# DBSchematics.net
KiCad netlist of a schematic drawn in EAGLE
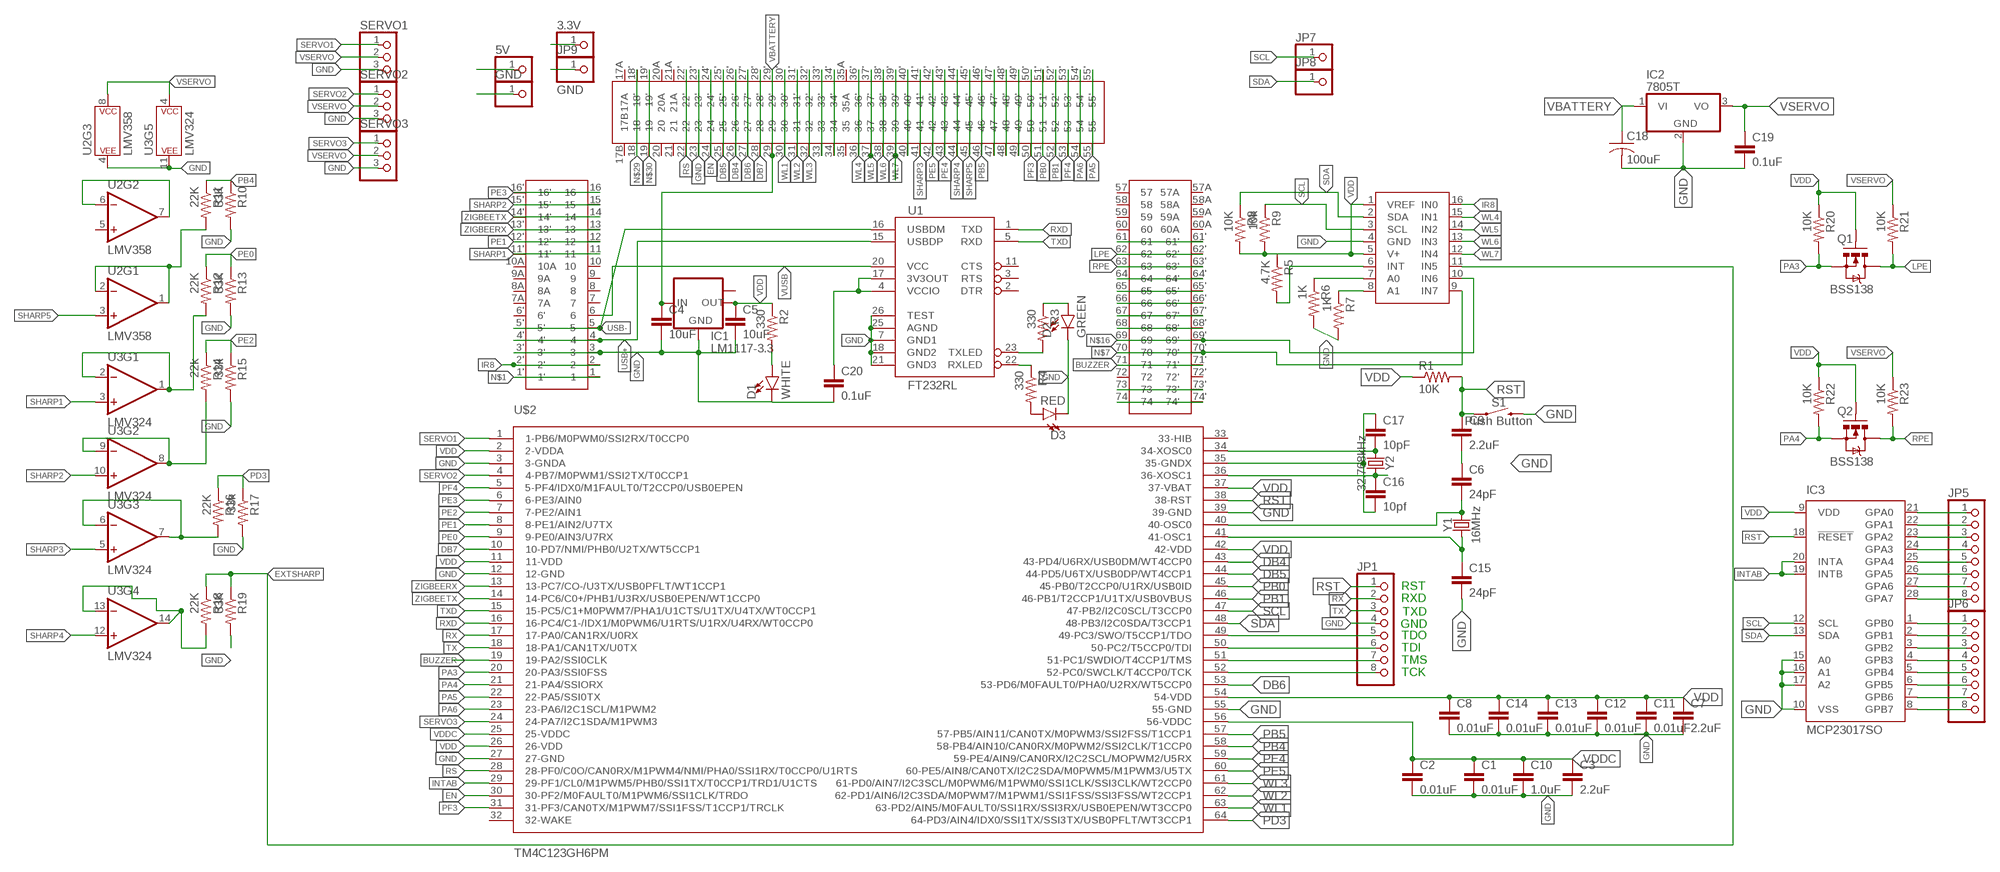
[diagram p0: schematic, sheet 1]

(export (version "E")
  (design (tool "Eeschema 10.0.6"))
  (components
    (comp (ref "3.3V")
      (value "PINHD-1X1")
      (footprint "eagle-import:1X01")
      (libsource (lib "eagle-import") (part "PINHD-1X1"))
    )
    (comp (ref "5V")
      (value "PINHD-1X1")
      (footprint "eagle-import:1X01")
      (libsource (lib "eagle-import") (part "PINHD-1X1"))
    )
    (comp (ref "C1")
      (value "0.01uF")
      (footprint "eagle-import:1206")
      (libsource (lib "eagle-import") (part "2.2UF-CERCAP-10009"))
    )
    (comp (ref "C2")
      (value "0.01uF")
      (footprint "eagle-import:1206")
      (libsource (lib "eagle-import") (part "2.2UF-CERCAP-10009"))
    )
    (comp (ref "C3")
      (value "2.2uF")
      (footprint "eagle-import:1206")
      (libsource (lib "eagle-import") (part "2.2UF-1206-50V-10%"))
    )
    (comp (ref "C4")
      (value "10uF")
      (footprint "eagle-import:1206")
      (libsource (lib "eagle-import") (part "10UF-1206-6.3V-20%"))
    )
    (comp (ref "C5")
      (value "10uF")
      (footprint "eagle-import:1206")
      (libsource (lib "eagle-import") (part "10UF-1206-6.3V-20%"))
    )
    (comp (ref "C6")
      (value "24pF")
      (footprint "eagle-import:1206")
      (libsource (lib "eagle-import") (part "2.2UF-CERCAP-10009"))
    )
    (comp (ref "C7")
      (value "2.2uF")
      (footprint "eagle-import:1206")
      (libsource (lib "eagle-import") (part "2.2UF-CERCAP-10009"))
    )
    (comp (ref "C8")
      (value "0.01uF")
      (footprint "eagle-import:1206")
      (libsource (lib "eagle-import") (part "2.2UF-CERCAP-10009"))
    )
    (comp (ref "C9")
      (value "2.2uF")
      (footprint "eagle-import:1206")
      (libsource (lib "eagle-import") (part "2.2UF-1206-50V-10%"))
    )
    (comp (ref "C10")
      (value "1.0uF")
      (footprint "eagle-import:1206")
      (libsource (lib "eagle-import") (part "1.0UF-1206-50V-10%"))
    )
    (comp (ref "C11")
      (value "0.01uF")
      (footprint "eagle-import:1206")
      (libsource (lib "eagle-import") (part "2.2UF-CERCAP-10009"))
    )
    (comp (ref "C12")
      (value "0.01uF")
      (footprint "eagle-import:1206")
      (libsource (lib "eagle-import") (part "2.2UF-CERCAP-10009"))
    )
    (comp (ref "C13")
      (value "0.01uF")
      (footprint "eagle-import:1206")
      (libsource (lib "eagle-import") (part "2.2UF-CERCAP-10009"))
    )
    (comp (ref "C14")
      (value "0.01uF")
      (footprint "eagle-import:1206")
      (libsource (lib "eagle-import") (part "2.2UF-CERCAP-10009"))
    )
    (comp (ref "C15")
      (value "24pF")
      (footprint "eagle-import:1206")
      (libsource (lib "eagle-import") (part "2.2UF-CERCAP-10009"))
    )
    (comp (ref "C16")
      (value "10pf")
      (footprint "eagle-import:1206")
      (libsource (lib "eagle-import") (part "2.2UF-CERCAP-10009"))
    )
    (comp (ref "C17")
      (value "10pF")
      (footprint "eagle-import:1206")
      (libsource (lib "eagle-import") (part "2.2UF-CERCAP-10009"))
    )
    (comp (ref "C18")
      (value "100uF")
      (footprint "eagle-import:C025-024X044")
      (libsource (lib "eagle-import") (part "C-US025-024X044"))
    )
    (comp (ref "C19")
      (value "0.1uF")
      (footprint "eagle-import:1206")
      (libsource (lib "eagle-import") (part "2.2UF-CERCAP-10009"))
    )
    (comp (ref "C20")
      (value "0.1uF")
      (footprint "eagle-import:1206")
      (libsource (lib "eagle-import") (part "10UF-1206-6.3V-20%"))
    )
    (comp (ref "D1")
      (value "WHITE")
      (footprint "eagle-import:LED-1206")
      (libsource (lib "eagle-import") (part "LED-WHITE1206"))
    )
    (comp (ref "D2")
      (value "GREEN")
      (footprint "eagle-import:LED-1206")
      (libsource (lib "eagle-import") (part "LED-WHITE1206"))
    )
    (comp (ref "D3")
      (value "RED")
      (footprint "eagle-import:LED-1206")
      (libsource (lib "eagle-import") (part "LED-WHITE1206"))
    )
    (comp (ref "GND")
      (value "PINHD-1X1")
      (footprint "eagle-import:1X01")
      (libsource (lib "eagle-import") (part "PINHD-1X1"))
    )
    (comp (ref "IC1")
      (value "LM1117-3.3")
      (footprint "eagle-import:SOT223")
      (libsource (lib "eagle-import") (part "LM1117IMPX-3.3"))
    )
    (comp (ref "IC2")
      (value "7805T")
      (footprint "eagle-import:TO220H")
      (libsource (lib "eagle-import") (part "78T05"))
    )
    (comp (ref "IC3")
      (value "MCP23017SO")
      (footprint "eagle-import:SO28W")
      (libsource (lib "eagle-import") (part "MCP23017SO"))
    )
    (comp (ref "JP1")
      (value "PINHD-1X8-3.5MM")
      (footprint "eagle-import:1X08-3.5MM")
      (libsource (lib "eagle-import") (part "PINHD-1X8-3.5MM"))
    )
    (comp (ref "JP5")
      (value "PINHD-1X8BIG")
      (footprint "eagle-import:1X08-BIG")
      (libsource (lib "eagle-import") (part "PINHD-1X8BIG"))
    )
    (comp (ref "JP6")
      (value "PINHD-1X8BIG")
      (footprint "eagle-import:1X08-BIG")
      (libsource (lib "eagle-import") (part "PINHD-1X8BIG"))
    )
    (comp (ref "JP7")
      (value "PINHD-1X1")
      (footprint "eagle-import:1X01")
      (libsource (lib "eagle-import") (part "PINHD-1X1"))
    )
    (comp (ref "JP8")
      (value "PINHD-1X1")
      (footprint "eagle-import:1X01")
      (libsource (lib "eagle-import") (part "PINHD-1X1"))
    )
    (comp (ref "JP9")
      (value "GND")
      (footprint "eagle-import:1X01")
      (libsource (lib "eagle-import") (part "PINHD-1X1"))
    )
    (comp (ref "Q1")
      (value "BSS138")
      (footprint "eagle-import:SOT23-3")
      (libsource (lib "eagle-import") (part "MOSFET-NCHANNELSMD"))
    )
    (comp (ref "Q2")
      (value "BSS138")
      (footprint "eagle-import:SOT23-3")
      (libsource (lib "eagle-import") (part "MOSFET-NCHANNELSMD"))
    )
    (comp (ref "R1")
      (value "10K")
      (footprint "eagle-import:M1206")
      (libsource (lib "eagle-import") (part "R-US_M1206"))
    )
    (comp (ref "R2")
      (value "330")
      (footprint "eagle-import:M1206")
      (libsource (lib "eagle-import") (part "R-US_M1206"))
    )
    (comp (ref "R3")
      (value "330")
      (footprint "eagle-import:M1206")
      (libsource (lib "eagle-import") (part "R-US_M1206"))
    )
    (comp (ref "R4")
      (value "330")
      (footprint "eagle-import:M1206")
      (libsource (lib "eagle-import") (part "R-US_M1206"))
    )
    (comp (ref "R5")
      (value "4.7K")
      (footprint "eagle-import:M1206")
      (libsource (lib "eagle-import") (part "R-US_M1206"))
    )
    (comp (ref "R6")
      (value "1K")
      (footprint "eagle-import:M1206")
      (libsource (lib "eagle-import") (part "R-US_M1206"))
    )
    (comp (ref "R7")
      (value "1K")
      (footprint "eagle-import:M1206")
      (libsource (lib "eagle-import") (part "R-US_M1206"))
    )
    (comp (ref "R8")
      (value "10K")
      (footprint "eagle-import:M1206")
      (libsource (lib "eagle-import") (part "R-US_M1206"))
    )
    (comp (ref "R9")
      (value "10k")
      (footprint "eagle-import:M1206")
      (libsource (lib "eagle-import") (part "R-US_M1206"))
    )
    (comp (ref "R10")
      (value "33K")
      (footprint "eagle-import:M1206")
      (libsource (lib "eagle-import") (part "R-US_M1206"))
    )
    (comp (ref "R11")
      (value "22K")
      (footprint "eagle-import:M1206")
      (libsource (lib "eagle-import") (part "R-US_M1206"))
    )
    (comp (ref "R12")
      (value "22K")
      (footprint "eagle-import:M1206")
      (libsource (lib "eagle-import") (part "R-US_M1206"))
    )
    (comp (ref "R13")
      (value "33K")
      (footprint "eagle-import:M1206")
      (libsource (lib "eagle-import") (part "R-US_M1206"))
    )
    (comp (ref "R14")
      (value "22k")
      (footprint "eagle-import:M1206")
      (libsource (lib "eagle-import") (part "R-US_M1206"))
    )
    (comp (ref "R15")
      (value "33k")
      (footprint "eagle-import:M1206")
      (libsource (lib "eagle-import") (part "R-US_M1206"))
    )
    (comp (ref "R16")
      (value "22K")
      (footprint "eagle-import:M1206")
      (libsource (lib "eagle-import") (part "R-US_M1206"))
    )
    (comp (ref "R17")
      (value "33k")
      (footprint "eagle-import:M1206")
      (libsource (lib "eagle-import") (part "R-US_M1206"))
    )
    (comp (ref "R18")
      (value "22K")
      (footprint "eagle-import:M1206")
      (libsource (lib "eagle-import") (part "R-US_M1206"))
    )
    (comp (ref "R19")
      (value "33K")
      (footprint "eagle-import:M1206")
      (libsource (lib "eagle-import") (part "R-US_M1206"))
    )
    (comp (ref "R20")
      (value "10K")
      (footprint "eagle-import:1206")
      (libsource (lib "eagle-import") (part "RESISTOR1206"))
    )
    (comp (ref "R21")
      (value "10K")
      (footprint "eagle-import:1206")
      (libsource (lib "eagle-import") (part "RESISTOR1206"))
    )
    (comp (ref "R22")
      (value "10K")
      (footprint "eagle-import:1206")
      (libsource (lib "eagle-import") (part "RESISTOR1206"))
    )
    (comp (ref "R23")
      (value "10K")
      (footprint "eagle-import:1206")
      (libsource (lib "eagle-import") (part "RESISTOR1206"))
    )
    (comp (ref "S1")
      (value "Push Button")
      (footprint "eagle-import:TACTILE_SWITCH_PTH_6.0MM")
      (libsource (lib "eagle-import") (part "MOMENTARY-SWITCH-SPST-PTH-6.0MM"))
    )
    (comp (ref "SERVO1")
      (value "PINHD-1X3")
      (footprint "eagle-import:1X03")
      (libsource (lib "eagle-import") (part "PINHD-1X3"))
    )
    (comp (ref "SERVO2")
      (value "PINHD-1X3")
      (footprint "eagle-import:1X03")
      (libsource (lib "eagle-import") (part "PINHD-1X3"))
    )
    (comp (ref "SERVO3")
      (value "PINHD-1X3")
      (footprint "eagle-import:1X03")
      (libsource (lib "eagle-import") (part "PINHD-1X3"))
    )
    (comp (ref "U$1")
      (value "DAUGHTERBOARDDAUGHTERBOARD")
      (footprint "eagle-import:DAUGHTERBOARD")
      (libsource (lib "eagle-import") (part "DAUGHTERBOARDDAUGHTERBOARD"))
    )
    (comp (ref "U$2")
      (value "TM4C123GH6PM")
      (footprint "eagle-import:LQFP")
      (libsource (lib "eagle-import") (part "TM4C123GH6PMS-PQFP-G64"))
    )
    (comp (ref "U$3")
      (value "ADC128D818")
      (footprint "eagle-import:ADC12_SD")
      (libsource (lib "eagle-import") (part "ADC128D818"))
    )
    (comp (ref "U1")
      (value "FT232RL")
      (footprint "eagle-import:SSOP28DB")
      (libsource (lib "eagle-import") (part "FT232RL-BASICSSOP"))
    )
    (comp (ref "U2")
      (value "LMV358")
      (footprint "eagle-import:SO08")
      (libsource (lib "eagle-import") (part "LMV358SOIC"))
    )
    (comp (ref "U3")
      (value "LMV324")
      (footprint "eagle-import:SO14")
      (libsource (lib "eagle-import") (part "LMV324"))
    )
    (comp (ref "Y1")
      (value "16MHz")
      (footprint "eagle-import:HC49US")
      (libsource (lib "eagle-import") (part "CRYSTAL-16MHZPTH-HC49US"))
    )
    (comp (ref "Y2")
      (value "32.768kHz")
      (footprint "eagle-import:CRYSTAL-PTH-2X6-CYL")
      (libsource (lib "eagle-import") (part "CRYSTAL-32.768KHZPTH-2X6"))
    )
  )
  (nets
    (net (code "1") (name "BUZZER") (class "Default")
      (node (ref "U$1") (pin "71") (pinfunction "71_71") (pintype "output"))
      (node (ref "U$1") (pin "71'") (pinfunction "71'_71'") (pintype "output"))
      (node (ref "U$2") (pin "19") (pinfunction "19-PA2/SSI0CLK_19") (pintype "bidirectional"))
    )
    (net (code "2") (name "DB4") (class "Default")
      (node (ref "U$1") (pin "26") (pinfunction "26_26") (pintype "output"))
      (node (ref "U$1") (pin "26'") (pinfunction "26'_26'") (pintype "output"))
      (node (ref "U$2") (pin "43") (pinfunction "43-PD4/U6RX/USB0DM/WT4CCP0_43") (pintype "bidirectional"))
    )
    (net (code "3") (name "DB5") (class "Default")
      (node (ref "U$1") (pin "25") (pinfunction "25_25") (pintype "output"))
      (node (ref "U$1") (pin "25'") (pinfunction "25'_25'") (pintype "output"))
      (node (ref "U$2") (pin "44") (pinfunction "44-PD5/U6TX/USB0DP/WT4CCP1_44") (pintype "bidirectional"))
    )
    (net (code "4") (name "DB6") (class "Default")
      (node (ref "U$1") (pin "27") (pinfunction "27_27") (pintype "output"))
      (node (ref "U$1") (pin "27'") (pinfunction "27'_27'") (pintype "output"))
      (node (ref "U$2") (pin "53") (pinfunction "53-PD6/M0FAULT0/PHA0/U2RX/WT5CCP0_53") (pintype "bidirectional"))
    )
    (net (code "5") (name "DB7") (class "Default")
      (node (ref "U$1") (pin "28") (pinfunction "28_28") (pintype "output"))
      (node (ref "U$1") (pin "28'") (pinfunction "28'_28'") (pintype "output"))
      (node (ref "U$2") (pin "10") (pinfunction "10-PD7/NMI/PHB0/U2TX/WT5CCP1_10") (pintype "bidirectional"))
    )
    (net (code "6") (name "EN") (class "Default")
      (node (ref "U$1") (pin "24") (pinfunction "24_24") (pintype "output"))
      (node (ref "U$1") (pin "24'") (pinfunction "24'_24'") (pintype "output"))
      (node (ref "U$2") (pin "30") (pinfunction "30-PF2/M0FAULT0/M1PWM6/SSI1CLK/TRDO_30") (pintype "bidirectional"))
    )
    (net (code "7") (name "EXTSHARP") (class "Default")
      (node (ref "R18") (pin "1") (pinfunction "1_1") (pintype "passive"))
      (node (ref "R19") (pin "1") (pinfunction "1_1") (pintype "passive"))
      (node (ref "U$3") (pin "11") (pinfunction "IN5_11") (pintype "bidirectional"))
    )
    (net (code "8") (name "GND") (class "Default")
      (node (ref "C1") (pin "2") (pinfunction "2_2") (pintype "passive"))
      (node (ref "C10") (pin "2") (pinfunction "2_2") (pintype "passive"))
      (node (ref "C11") (pin "2") (pinfunction "2_2") (pintype "passive"))
      (node (ref "C12") (pin "2") (pinfunction "2_2") (pintype "passive"))
      (node (ref "C13") (pin "2") (pinfunction "2_2") (pintype "passive"))
      (node (ref "C14") (pin "2") (pinfunction "2_2") (pintype "passive"))
      (node (ref "C15") (pin "2") (pinfunction "2_2") (pintype "passive"))
      (node (ref "C18") (pin "2") (pinfunction "2_2") (pintype "passive"))
      (node (ref "C19") (pin "2") (pinfunction "2_2") (pintype "passive"))
      (node (ref "C2") (pin "2") (pinfunction "2_2") (pintype "passive"))
      (node (ref "C20") (pin "2") (pinfunction "2_2") (pintype "passive"))
      (node (ref "C3") (pin "2") (pinfunction "2_2") (pintype "passive"))
      (node (ref "C4") (pin "2") (pinfunction "2_2") (pintype "passive"))
      (node (ref "C5") (pin "2") (pinfunction "2_2") (pintype "passive"))
      (node (ref "C6") (pin "1") (pinfunction "1_1") (pintype "passive"))
      (node (ref "C7") (pin "2") (pinfunction "2_2") (pintype "passive"))
      (node (ref "C8") (pin "2") (pinfunction "2_2") (pintype "passive"))
      (node (ref "C9") (pin "2") (pinfunction "2_2") (pintype "passive"))
      (node (ref "D1") (pin "C") (pinfunction "C_C") (pintype "passive"))
      (node (ref "D2") (pin "C") (pinfunction "C_C") (pintype "passive"))
      (node (ref "D3") (pin "C") (pinfunction "C_C") (pintype "passive"))
      (node (ref "GND") (pin "1") (pinfunction "1_1") (pintype "passive"))
      (node (ref "IC1") (pin "1") (pinfunction "GND_1") (pintype "input"))
      (node (ref "IC2") (pin "2") (pinfunction "GND_2") (pintype "passive"))
      (node (ref "IC3") (pin "10") (pinfunction "VSS_10") (pintype "power_in"))
      (node (ref "IC3") (pin "15") (pinfunction "A0_15") (pintype "input"))
      (node (ref "IC3") (pin "16") (pinfunction "A1_16") (pintype "input"))
      (node (ref "IC3") (pin "17") (pinfunction "A2_17") (pintype "input"))
      (node (ref "JP1") (pin "4") (pinfunction "4_4") (pintype "passive"))
      (node (ref "JP9") (pin "1") (pinfunction "1_1") (pintype "passive"))
      (node (ref "R10") (pin "2") (pinfunction "2_2") (pintype "passive"))
      (node (ref "R13") (pin "2") (pinfunction "2_2") (pintype "passive"))
      (node (ref "R15") (pin "2") (pinfunction "2_2") (pintype "passive"))
      (node (ref "R17") (pin "2") (pinfunction "2_2") (pintype "passive"))
      (node (ref "R19") (pin "2") (pinfunction "2_2") (pintype "passive"))
      (node (ref "R6") (pin "2") (pinfunction "2_2") (pintype "passive"))
      (node (ref "R7") (pin "2") (pinfunction "2_2") (pintype "passive"))
      (node (ref "S1") (pin "3") (pinfunction "2_3") (pintype "passive"))
      (node (ref "SERVO1") (pin "3") (pinfunction "3_3") (pintype "passive"))
      (node (ref "SERVO2") (pin "3") (pinfunction "3_3") (pintype "passive"))
      (node (ref "SERVO3") (pin "3") (pinfunction "3_3") (pintype "passive"))
      (node (ref "U$1") (pin "23") (pinfunction "23_23") (pintype "output"))
      (node (ref "U$1") (pin "23'") (pinfunction "23'_23'") (pintype "output"))
      (node (ref "U$1") (pin "3") (pinfunction "3_3") (pintype "output"))
      (node (ref "U$1") (pin "3'") (pinfunction "3'_3'") (pintype "output"))
      (node (ref "U$2") (pin "12") (pinfunction "12-GND_12") (pintype "bidirectional"))
      (node (ref "U$2") (pin "27") (pinfunction "27-GND_27") (pintype "bidirectional"))
      (node (ref "U$2") (pin "3") (pinfunction "3-GNDA_3") (pintype "bidirectional"))
      (node (ref "U$2") (pin "39") (pinfunction "39-GND_39") (pintype "bidirectional"))
      (node (ref "U$2") (pin "55") (pinfunction "55-GND_55") (pintype "bidirectional"))
      (node (ref "U$3") (pin "4") (pinfunction "GND_4") (pintype "bidirectional"))
      (node (ref "U1") (pin "18") (pinfunction "GND2_18") (pintype "power_in"))
      (node (ref "U1") (pin "21") (pinfunction "GND3_21") (pintype "power_in"))
      (node (ref "U1") (pin "25") (pinfunction "AGND_25") (pintype "power_in"))
      (node (ref "U1") (pin "26") (pinfunction "TEST_26") (pintype "input"))
      (node (ref "U1") (pin "7") (pinfunction "GND1_7") (pintype "power_in"))
      (node (ref "U2") (pin "4") (pinfunction "P$V-_4") (pintype "bidirectional"))
      (node (ref "U3") (pin "11") (pinfunction "P$V-_11") (pintype "bidirectional"))
    )
    (net (code "9") (name "INTAB") (class "Default")
      (node (ref "IC3") (pin "19") (pinfunction "INTB_19") (pintype "output"))
      (node (ref "IC3") (pin "20") (pinfunction "INTA_20") (pintype "output"))
      (node (ref "U$2") (pin "29") (pinfunction "29-PF1/CL0/M1PWM5/PHB0/SSI1TX/T0CCP1/TRD1/U1CTS_29") (pintype "bidirectional"))
    )
    (net (code "10") (name "IR8") (class "Default")
      (node (ref "U$1") (pin "2") (pinfunction "2_2") (pintype "output"))
      (node (ref "U$1") (pin "2'") (pinfunction "2'_2'") (pintype "output"))
      (node (ref "U$3") (pin "16") (pinfunction "IN0_16") (pintype "bidirectional"))
    )
    (net (code "11") (name "LPE") (class "Default")
      (node (ref "Q1") (pin "3") (pinfunction "D_3") (pintype "passive"))
      (node (ref "R21") (pin "2") (pinfunction "2_2") (pintype "passive"))
      (node (ref "U$1") (pin "62") (pinfunction "62_62") (pintype "output"))
      (node (ref "U$1") (pin "62'") (pinfunction "62'_62'") (pintype "output"))
    )
    (net (code "12") (name "N$1") (class "Default")
      (node (ref "U$1") (pin "1") (pinfunction "1_1") (pintype "output"))
      (node (ref "U$1") (pin "1'") (pinfunction "1'_1'") (pintype "output"))
    )
    (net (code "13") (name "N$7") (class "Default")
      (node (ref "U$1") (pin "70") (pinfunction "70_70") (pintype "output"))
      (node (ref "U$1") (pin "70'") (pinfunction "70'_70'") (pintype "output"))
      (node (ref "U$3") (pin "9") (pinfunction "IN7_9") (pintype "bidirectional"))
    )
    (net (code "14") (name "N$16") (class "Default")
      (node (ref "U$1") (pin "69") (pinfunction "69_69") (pintype "output"))
      (node (ref "U$1") (pin "69'") (pinfunction "69'_69'") (pintype "output"))
      (node (ref "U$3") (pin "10") (pinfunction "IN6_10") (pintype "bidirectional"))
    )
    (net (code "15") (name "N$29") (class "Default")
      (node (ref "U$1") (pin "18") (pinfunction "18_18") (pintype "output"))
      (node (ref "U$1") (pin "18'") (pinfunction "18'_18'") (pintype "output"))
    )
    (net (code "16") (name "N$30") (class "Default")
      (node (ref "U$1") (pin "19") (pinfunction "19_19") (pintype "output"))
      (node (ref "U$1") (pin "19'") (pinfunction "19'_19'") (pintype "output"))
    )
    (net (code "17") (name "Net-(D1-PadA)") (class "Default")
      (node (ref "D1") (pin "A") (pinfunction "A_A") (pintype "passive"))
      (node (ref "R2") (pin "2") (pinfunction "2_2") (pintype "passive"))
    )
    (net (code "18") (name "Net-(D2-PadA)") (class "Default")
      (node (ref "D2") (pin "A") (pinfunction "A_A") (pintype "passive"))
      (node (ref "R3") (pin "1") (pinfunction "1_1") (pintype "passive"))
    )
    (net (code "19") (name "Net-(D3-PadA)") (class "Default")
      (node (ref "D3") (pin "A") (pinfunction "A_A") (pintype "passive"))
      (node (ref "R4") (pin "2") (pinfunction "2_2") (pintype "passive"))
    )
    (net (code "20") (name "Net-(IC3-GPA0)") (class "Default")
      (node (ref "IC3") (pin "21") (pinfunction "GPA0_21") (pintype "bidirectional"))
      (node (ref "JP5") (pin "1") (pinfunction "1_1") (pintype "passive"))
    )
    (net (code "21") (name "Net-(IC3-GPA1)") (class "Default")
      (node (ref "IC3") (pin "22") (pinfunction "GPA1_22") (pintype "bidirectional"))
      (node (ref "JP5") (pin "2") (pinfunction "2_2") (pintype "passive"))
    )
    (net (code "22") (name "Net-(IC3-GPA2)") (class "Default")
      (node (ref "IC3") (pin "23") (pinfunction "GPA2_23") (pintype "bidirectional"))
      (node (ref "JP5") (pin "3") (pinfunction "3_3") (pintype "passive"))
    )
    (net (code "23") (name "Net-(IC3-GPA3)") (class "Default")
      (node (ref "IC3") (pin "24") (pinfunction "GPA3_24") (pintype "bidirectional"))
      (node (ref "JP5") (pin "4") (pinfunction "4_4") (pintype "passive"))
    )
    (net (code "24") (name "Net-(IC3-GPA4)") (class "Default")
      (node (ref "IC3") (pin "25") (pinfunction "GPA4_25") (pintype "bidirectional"))
      (node (ref "JP5") (pin "5") (pinfunction "5_5") (pintype "passive"))
    )
    (net (code "25") (name "Net-(IC3-GPA5)") (class "Default")
      (node (ref "IC3") (pin "26") (pinfunction "GPA5_26") (pintype "bidirectional"))
      (node (ref "JP5") (pin "6") (pinfunction "6_6") (pintype "passive"))
    )
    (net (code "26") (name "Net-(IC3-GPA6)") (class "Default")
      (node (ref "IC3") (pin "27") (pinfunction "GPA6_27") (pintype "bidirectional"))
      (node (ref "JP5") (pin "7") (pinfunction "7_7") (pintype "passive"))
    )
    (net (code "27") (name "Net-(IC3-GPA7)") (class "Default")
      (node (ref "IC3") (pin "28") (pinfunction "GPA7_28") (pintype "bidirectional"))
      (node (ref "JP5") (pin "8") (pinfunction "8_8") (pintype "passive"))
    )
    (net (code "28") (name "Net-(IC3-GPB0)") (class "Default")
      (node (ref "IC3") (pin "1") (pinfunction "GPB0_1") (pintype "bidirectional"))
      (node (ref "JP6") (pin "1") (pinfunction "1_1") (pintype "passive"))
    )
    (net (code "29") (name "Net-(IC3-GPB1)") (class "Default")
      (node (ref "IC3") (pin "2") (pinfunction "GPB1_2") (pintype "bidirectional"))
      (node (ref "JP6") (pin "2") (pinfunction "2_2") (pintype "passive"))
    )
    (net (code "30") (name "Net-(IC3-GPB2)") (class "Default")
      (node (ref "IC3") (pin "3") (pinfunction "GPB2_3") (pintype "bidirectional"))
      (node (ref "JP6") (pin "3") (pinfunction "3_3") (pintype "passive"))
    )
    (net (code "31") (name "Net-(IC3-GPB3)") (class "Default")
      (node (ref "IC3") (pin "4") (pinfunction "GPB3_4") (pintype "bidirectional"))
      (node (ref "JP6") (pin "4") (pinfunction "4_4") (pintype "passive"))
    )
    (net (code "32") (name "Net-(IC3-GPB4)") (class "Default")
      (node (ref "IC3") (pin "5") (pinfunction "GPB4_5") (pintype "bidirectional"))
      (node (ref "JP6") (pin "5") (pinfunction "5_5") (pintype "passive"))
    )
    (net (code "33") (name "Net-(IC3-GPB5)") (class "Default")
      (node (ref "IC3") (pin "6") (pinfunction "GPB5_6") (pintype "bidirectional"))
      (node (ref "JP6") (pin "6") (pinfunction "6_6") (pintype "passive"))
    )
    (net (code "34") (name "Net-(IC3-GPB6)") (class "Default")
      (node (ref "IC3") (pin "7") (pinfunction "GPB6_7") (pintype "bidirectional"))
      (node (ref "JP6") (pin "7") (pinfunction "7_7") (pintype "passive"))
    )
    (net (code "35") (name "Net-(IC3-GPB7)") (class "Default")
      (node (ref "IC3") (pin "8") (pinfunction "GPB7_8") (pintype "bidirectional"))
      (node (ref "JP6") (pin "8") (pinfunction "8_8") (pintype "passive"))
    )
    (net (code "36") (name "Net-(U$1-Pad33')") (class "Default")
      (node (ref "U$1") (pin "33") (pinfunction "33_33") (pintype "output"))
      (node (ref "U$1") (pin "33'") (pinfunction "33'_33'") (pintype "output"))
    )
    (net (code "37") (name "Net-(U$1-Pad34')") (class "Default")
      (node (ref "U$1") (pin "34") (pinfunction "34_34") (pintype "output"))
      (node (ref "U$1") (pin "34'") (pinfunction "34'_34'") (pintype "output"))
    )
    (net (code "38") (name "Net-(U$1-Pad40')") (class "Default")
      (node (ref "U$1") (pin "40") (pinfunction "40_40") (pintype "output"))
      (node (ref "U$1") (pin "40'") (pinfunction "40'_40'") (pintype "output"))
    )
    (net (code "39") (name "Net-(U$1-Pad47')") (class "Default")
      (node (ref "U$1") (pin "47") (pinfunction "47_47") (pintype "output"))
      (node (ref "U$1") (pin "47'") (pinfunction "47'_47'") (pintype "output"))
    )
    (net (code "40") (name "Net-(U$1-Pad48')") (class "Default")
      (node (ref "U$1") (pin "48") (pinfunction "48_48") (pintype "output"))
      (node (ref "U$1") (pin "48'") (pinfunction "48'_48'") (pintype "output"))
    )
    (net (code "41") (name "Net-(U$1-Pad49')") (class "Default")
      (node (ref "U$1") (pin "49") (pinfunction "49_49") (pintype "output"))
      (node (ref "U$1") (pin "49'") (pinfunction "49'_49'") (pintype "output"))
    )
    (net (code "42") (name "Net-(U$1-Pad61')") (class "Default")
      (node (ref "U$1") (pin "61") (pinfunction "61_61") (pintype "output"))
      (node (ref "U$1") (pin "61'") (pinfunction "61'_61'") (pintype "output"))
    )
    (net (code "43") (name "Net-(U$1-Pad64')") (class "Default")
      (node (ref "U$1") (pin "64") (pinfunction "64_64") (pintype "output"))
      (node (ref "U$1") (pin "64'") (pinfunction "64'_64'") (pintype "output"))
    )
    (net (code "44") (name "Net-(U$1-Pad65')") (class "Default")
      (node (ref "U$1") (pin "65") (pinfunction "65_65") (pintype "output"))
      (node (ref "U$1") (pin "65'") (pinfunction "65'_65'") (pintype "output"))
    )
    (net (code "45") (name "Net-(U$1-Pad66')") (class "Default")
      (node (ref "U$1") (pin "66") (pinfunction "66_66") (pintype "output"))
      (node (ref "U$1") (pin "66'") (pinfunction "66'_66'") (pintype "output"))
    )
    (net (code "46") (name "Net-(U$1-Pad67')") (class "Default")
      (node (ref "U$1") (pin "67") (pinfunction "67_67") (pintype "output"))
      (node (ref "U$1") (pin "67'") (pinfunction "67'_67'") (pintype "output"))
    )
    (net (code "47") (name "Net-(U$1-Pad68')") (class "Default")
      (node (ref "U$1") (pin "68") (pinfunction "68_68") (pintype "output"))
      (node (ref "U$1") (pin "68'") (pinfunction "68'_68'") (pintype "output"))
    )
    (net (code "48") (name "Net-(U$1-Pad73')") (class "Default")
      (node (ref "U$1") (pin "73") (pinfunction "73_73") (pintype "output"))
      (node (ref "U$1") (pin "73'") (pinfunction "73'_73'") (pintype "output"))
    )
    (net (code "49") (name "Net-(U$1-Pad74')") (class "Default")
      (node (ref "U$1") (pin "74") (pinfunction "74_74") (pintype "output"))
      (node (ref "U$1") (pin "74'") (pinfunction "74'_74'") (pintype "output"))
    )
    (net (code "50") (name "Net-(U$2-34-XOSC0)") (class "Default")
      (node (ref "C17") (pin "2") (pinfunction "2_2") (pintype "passive"))
      (node (ref "U$2") (pin "34") (pinfunction "34-XOSC0_34") (pintype "bidirectional"))
      (node (ref "Y2") (pin "1") (pinfunction "1_1") (pintype "passive"))
    )
    (net (code "51") (name "Net-(U$2-35-GNDX)") (class "Default")
      (node (ref "C16") (pin "2") (pinfunction "2_2") (pintype "passive"))
      (node (ref "C17") (pin "1") (pinfunction "1_1") (pintype "passive"))
      (node (ref "U$2") (pin "35") (pinfunction "35-GNDX_35") (pintype "bidirectional"))
    )
    (net (code "52") (name "Net-(U$2-36-XOSC1)") (class "Default")
      (node (ref "C16") (pin "1") (pinfunction "1_1") (pintype "passive"))
      (node (ref "U$2") (pin "36") (pinfunction "36-XOSC1_36") (pintype "bidirectional"))
      (node (ref "Y2") (pin "2") (pinfunction "2_2") (pintype "passive"))
    )
    (net (code "53") (name "Net-(U$2-40-OSC0)") (class "Default")
      (node (ref "C6") (pin "2") (pinfunction "2_2") (pintype "passive"))
      (node (ref "U$2") (pin "40") (pinfunction "40-OSC0_40") (pintype "bidirectional"))
      (node (ref "Y1") (pin "2") (pinfunction "2_2") (pintype "passive"))
    )
    (net (code "54") (name "Net-(U$2-41-OSC1)") (class "Default")
      (node (ref "C15") (pin "1") (pinfunction "1_1") (pintype "passive"))
      (node (ref "U$2") (pin "41") (pinfunction "41-OSC1_41") (pintype "bidirectional"))
      (node (ref "Y1") (pin "1") (pinfunction "1_1") (pintype "passive"))
    )
    (net (code "55") (name "Net-(U$2-49-PC3{slash}SWO{slash}T5CCP1{slash}TDO)") (class "Default")
      (node (ref "JP1") (pin "5") (pinfunction "5_5") (pintype "passive"))
      (node (ref "U$2") (pin "49") (pinfunction "49-PC3/SWO/T5CCP1/TDO_49") (pintype "bidirectional"))
    )
    (net (code "56") (name "Net-(U$2-50-PC2{slash}T5CCP0{slash}TDI)") (class "Default")
      (node (ref "JP1") (pin "6") (pinfunction "6_6") (pintype "passive"))
      (node (ref "U$2") (pin "50") (pinfunction "50-PC2/T5CCP0/TDI_50") (pintype "bidirectional"))
    )
    (net (code "57") (name "Net-(U$2-51-PC1{slash}SWDIO{slash}T4CCP1{slash}TMS)") (class "Default")
      (node (ref "JP1") (pin "7") (pinfunction "7_7") (pintype "passive"))
      (node (ref "U$2") (pin "51") (pinfunction "51-PC1/SWDIO/T4CCP1/TMS_51") (pintype "bidirectional"))
    )
    (net (code "58") (name "Net-(U$2-52-PC0{slash}SWCLK{slash}T4CCP0{slash}TCK)") (class "Default")
      (node (ref "JP1") (pin "8") (pinfunction "8_8") (pintype "passive"))
      (node (ref "U$2") (pin "52") (pinfunction "52-PC0/SWCLK/T4CCP0/TCK_52") (pintype "bidirectional"))
    )
    (net (code "59") (name "Net-(U$3-A0)") (class "Default")
      (node (ref "R6") (pin "1") (pinfunction "1_1") (pintype "passive"))
      (node (ref "U$3") (pin "7") (pinfunction "A0_7") (pintype "bidirectional"))
    )
    (net (code "60") (name "Net-(U$3-A1)") (class "Default")
      (node (ref "R7") (pin "1") (pinfunction "1_1") (pintype "passive"))
      (node (ref "U$3") (pin "8") (pinfunction "A1_8") (pintype "bidirectional"))
    )
    (net (code "61") (name "Net-(U$3-INT)") (class "Default")
      (node (ref "R5") (pin "2") (pinfunction "2_2") (pintype "passive"))
      (node (ref "U$3") (pin "6") (pinfunction "INT_6") (pintype "bidirectional"))
    )
    (net (code "62") (name "Net-(U1-3V3OUT)") (class "Default")
      (node (ref "C20") (pin "1") (pinfunction "1_1") (pintype "passive"))
      (node (ref "U1") (pin "17") (pinfunction "3V3OUT_17") (pintype "output"))
      (node (ref "U1") (pin "4") (pinfunction "VCCIO_4") (pintype "power_in"))
    )
    (net (code "63") (name "Net-(U1-RXLED)") (class "Default")
      (node (ref "R4") (pin "1") (pinfunction "1_1") (pintype "passive"))
      (node (ref "U1") (pin "22") (pinfunction "RXLED_22") (pintype "bidirectional"))
    )
    (net (code "64") (name "Net-(U1-TXLED)") (class "Default")
      (node (ref "R3") (pin "2") (pinfunction "2_2") (pintype "passive"))
      (node (ref "U1") (pin "23") (pinfunction "TXLED_23") (pintype "bidirectional"))
    )
    (net (code "65") (name "Net-(U2A--IN)") (class "Default")
      (node (ref "R11") (pin "2") (pinfunction "2_2") (pintype "passive"))
      (node (ref "U2") (pin "1") (pinfunction "OUT_1") (pintype "output"))
      (node (ref "U2") (pin "2") (pinfunction "-IN_2") (pintype "input"))
    )
    (net (code "66") (name "Net-(U2B--IN)") (class "Default")
      (node (ref "U2") (pin "6") (pinfunction "-IN_6") (pintype "input"))
      (node (ref "U2") (pin "7") (pinfunction "OUT_7") (pintype "output"))
    )
    (net (code "67") (name "Net-(U3A--IN)") (class "Default")
      (node (ref "R12") (pin "2") (pinfunction "2_2") (pintype "passive"))
      (node (ref "U3") (pin "1") (pinfunction "OUT_1") (pintype "output"))
      (node (ref "U3") (pin "2") (pinfunction "-IN_2") (pintype "input"))
    )
    (net (code "68") (name "Net-(U3B--IN)") (class "Default")
      (node (ref "R14") (pin "2") (pinfunction "2_2") (pintype "passive"))
      (node (ref "U3") (pin "8") (pinfunction "OUT_8") (pintype "output"))
      (node (ref "U3") (pin "9") (pinfunction "-IN_9") (pintype "input"))
    )
    (net (code "69") (name "Net-(U3C--IN)") (class "Default")
      (node (ref "R16") (pin "2") (pinfunction "2_2") (pintype "passive"))
      (node (ref "U3") (pin "6") (pinfunction "-IN_6") (pintype "input"))
      (node (ref "U3") (pin "7") (pinfunction "OUT_7") (pintype "output"))
    )
    (net (code "70") (name "Net-(U3D--IN)") (class "Default")
      (node (ref "R18") (pin "2") (pinfunction "2_2") (pintype "passive"))
      (node (ref "U3") (pin "13") (pinfunction "-IN_13") (pintype "input"))
      (node (ref "U3") (pin "14") (pinfunction "OUT_14") (pintype "output"))
    )
    (net (code "71") (name "PA3") (class "Default")
      (node (ref "Q1") (pin "2") (pinfunction "S_2") (pintype "passive"))
      (node (ref "R20") (pin "2") (pinfunction "2_2") (pintype "passive"))
      (node (ref "U$2") (pin "20") (pinfunction "20-PA3/SSI0FSS_20") (pintype "bidirectional"))
    )
    (net (code "72") (name "PA4") (class "Default")
      (node (ref "Q2") (pin "2") (pinfunction "S_2") (pintype "passive"))
      (node (ref "R22") (pin "2") (pinfunction "2_2") (pintype "passive"))
      (node (ref "U$2") (pin "21") (pinfunction "21-PA4/SSIORX_21") (pintype "bidirectional"))
    )
    (net (code "73") (name "PA5") (class "Default")
      (node (ref "U$1") (pin "55") (pinfunction "55_55") (pintype "output"))
      (node (ref "U$1") (pin "55'") (pinfunction "55'_55'") (pintype "output"))
      (node (ref "U$2") (pin "22") (pinfunction "22-PA5/SSI0TX_22") (pintype "bidirectional"))
    )
    (net (code "74") (name "PA6") (class "Default")
      (node (ref "U$1") (pin "54") (pinfunction "54_54") (pintype "output"))
      (node (ref "U$1") (pin "54'") (pinfunction "54'_54'") (pintype "output"))
      (node (ref "U$2") (pin "23") (pinfunction "23-PA6/I2C1SCL/M1PWM2_23") (pintype "bidirectional"))
    )
    (net (code "75") (name "PB0") (class "Default")
      (node (ref "U$1") (pin "51") (pinfunction "51_51") (pintype "output"))
      (node (ref "U$1") (pin "51'") (pinfunction "51'_51'") (pintype "output"))
      (node (ref "U$2") (pin "45") (pinfunction "45-PB0/T2CCP0/U1RX/USB0ID_45") (pintype "bidirectional"))
    )
    (net (code "76") (name "PB1") (class "Default")
      (node (ref "U$1") (pin "52") (pinfunction "52_52") (pintype "output"))
      (node (ref "U$1") (pin "52'") (pinfunction "52'_52'") (pintype "output"))
      (node (ref "U$2") (pin "46") (pinfunction "46-PB1/T2CCP1/U1TX/USB0VBUS_46") (pintype "bidirectional"))
    )
    (net (code "77") (name "PB4") (class "Default")
      (node (ref "R10") (pin "1") (pinfunction "1_1") (pintype "passive"))
      (node (ref "R11") (pin "1") (pinfunction "1_1") (pintype "passive"))
      (node (ref "U$2") (pin "58") (pinfunction "58-PB4/AIN10/CAN0RX/M0PWM2/SSI2CLK/T1CCP0_58") (pintype "bidirectional"))
    )
    (net (code "78") (name "PB5") (class "Default")
      (node (ref "U$1") (pin "46") (pinfunction "46_46") (pintype "output"))
      (node (ref "U$1") (pin "46'") (pinfunction "46'_46'") (pintype "output"))
      (node (ref "U$2") (pin "57") (pinfunction "57-PB5/AIN11/CAN0TX/M0PWM3/SSI2FSS/T1CCP1_57") (pintype "bidirectional"))
    )
    (net (code "79") (name "PD3") (class "Default")
      (node (ref "R16") (pin "1") (pinfunction "1_1") (pintype "passive"))
      (node (ref "R17") (pin "1") (pinfunction "1_1") (pintype "passive"))
      (node (ref "U$2") (pin "64") (pinfunction "64-PD3/AIN4/IDX0/SSI1TX/SSI3TX/USB0PFLT/WT3CCP1_64") (pintype "bidirectional"))
    )
    (net (code "80") (name "PE0") (class "Default")
      (node (ref "R12") (pin "1") (pinfunction "1_1") (pintype "passive"))
      (node (ref "R13") (pin "1") (pinfunction "1_1") (pintype "passive"))
      (node (ref "U$2") (pin "9") (pinfunction "9-PE0/AIN3/U7RX_9") (pintype "bidirectional"))
    )
    (net (code "81") (name "PE1") (class "Default")
      (node (ref "U$1") (pin "12") (pinfunction "12_12") (pintype "output"))
      (node (ref "U$1") (pin "12'") (pinfunction "12'_12'") (pintype "output"))
      (node (ref "U$2") (pin "8") (pinfunction "8-PE1/AIN2/U7TX_8") (pintype "bidirectional"))
    )
    (net (code "82") (name "PE2") (class "Default")
      (node (ref "R14") (pin "1") (pinfunction "1_1") (pintype "passive"))
      (node (ref "R15") (pin "1") (pinfunction "1_1") (pintype "passive"))
      (node (ref "U$2") (pin "7") (pinfunction "7-PE2/AIN1_7") (pintype "bidirectional"))
    )
    (net (code "83") (name "PE3") (class "Default")
      (node (ref "U$1") (pin "16") (pinfunction "16_16") (pintype "output"))
      (node (ref "U$1") (pin "16'") (pinfunction "16'_16'") (pintype "output"))
      (node (ref "U$2") (pin "6") (pinfunction "6-PE3/AIN0_6") (pintype "bidirectional"))
    )
    (net (code "84") (name "PE4") (class "Default")
      (node (ref "U$1") (pin "43") (pinfunction "43_43") (pintype "output"))
      (node (ref "U$1") (pin "43'") (pinfunction "43'_43'") (pintype "output"))
      (node (ref "U$2") (pin "59") (pinfunction "59-PE4/AIN9/CAN0RX/I2C2SCL/MOPWM2/U5RX_59") (pintype "bidirectional"))
    )
    (net (code "85") (name "PE5") (class "Default")
      (node (ref "U$1") (pin "42") (pinfunction "42_42") (pintype "output"))
      (node (ref "U$1") (pin "42'") (pinfunction "42'_42'") (pintype "output"))
      (node (ref "U$2") (pin "60") (pinfunction "60-PE5/AIN8/CAN0TX/I2C2SDA/M0PWM5/M1PWM3/U5TX_60") (pintype "bidirectional"))
    )
    (net (code "86") (name "PF3") (class "Default")
      (node (ref "U$1") (pin "50") (pinfunction "50_50") (pintype "output"))
      (node (ref "U$1") (pin "50'") (pinfunction "50'_50'") (pintype "output"))
      (node (ref "U$2") (pin "31") (pinfunction "31-PF3/CAN0TX/M1PWM7/SSI1FSS/T1CCP1/TRCLK_31") (pintype "bidirectional"))
    )
    (net (code "87") (name "PF4") (class "Default")
      (node (ref "U$1") (pin "53") (pinfunction "53_53") (pintype "output"))
      (node (ref "U$1") (pin "53'") (pinfunction "53'_53'") (pintype "output"))
      (node (ref "U$2") (pin "5") (pinfunction "5-PF4/IDX0/M1FAULT0/T2CCP0/USB0EPEN_5") (pintype "bidirectional"))
    )
    (net (code "88") (name "RPE") (class "Default")
      (node (ref "Q2") (pin "3") (pinfunction "D_3") (pintype "passive"))
      (node (ref "R23") (pin "2") (pinfunction "2_2") (pintype "passive"))
      (node (ref "U$1") (pin "63") (pinfunction "63_63") (pintype "output"))
      (node (ref "U$1") (pin "63'") (pinfunction "63'_63'") (pintype "output"))
    )
    (net (code "89") (name "RS") (class "Default")
      (node (ref "U$1") (pin "22") (pinfunction "22_22") (pintype "output"))
      (node (ref "U$1") (pin "22'") (pinfunction "22'_22'") (pintype "output"))
      (node (ref "U$2") (pin "28") (pinfunction "28-PF0/C0O/CAN0RX/M1PWM4/NMI/PHA0/SSI1RX/T0CCP0/U1RTS_28") (pintype "bidirectional"))
    )
    (net (code "90") (name "RST") (class "Default")
      (node (ref "C9") (pin "1") (pinfunction "1_1") (pintype "passive"))
      (node (ref "IC3") (pin "18") (pinfunction "~{RESET}_18") (pintype "input"))
      (node (ref "JP1") (pin "1") (pinfunction "1_1") (pintype "passive"))
      (node (ref "R1") (pin "2") (pinfunction "2_2") (pintype "passive"))
      (node (ref "S1") (pin "1") (pinfunction "1_1") (pintype "passive"))
      (node (ref "U$2") (pin "38") (pinfunction "38-RST_38") (pintype "bidirectional"))
    )
    (net (code "91") (name "RX") (class "Default")
      (node (ref "JP1") (pin "2") (pinfunction "2_2") (pintype "passive"))
      (node (ref "U$2") (pin "17") (pinfunction "17-PA0/CAN1RX/U0RX_17") (pintype "bidirectional"))
    )
    (net (code "92") (name "RXD") (class "Default")
      (node (ref "U$2") (pin "16") (pinfunction "16-PC4/C1-/IDX1/M0PWM6/U1RTS/U1RX/U4RX/WT0CCP0_16") (pintype "bidirectional"))
      (node (ref "U1") (pin "1") (pinfunction "TXD_1") (pintype "output"))
    )
    (net (code "93") (name "SCL") (class "Default")
      (node (ref "IC3") (pin "12") (pinfunction "SCL_12") (pintype "input"))
      (node (ref "JP7") (pin "1") (pinfunction "1_1") (pintype "passive"))
      (node (ref "R9") (pin "1") (pinfunction "1_1") (pintype "passive"))
      (node (ref "U$2") (pin "47") (pinfunction "47-PB2/I2C0SCL/T3CCP0_47") (pintype "bidirectional"))
      (node (ref "U$3") (pin "3") (pinfunction "SCL_3") (pintype "bidirectional"))
    )
    (net (code "94") (name "SDA") (class "Default")
      (node (ref "IC3") (pin "13") (pinfunction "SDA_13") (pintype "bidirectional"))
      (node (ref "JP8") (pin "1") (pinfunction "1_1") (pintype "passive"))
      (node (ref "R8") (pin "1") (pinfunction "1_1") (pintype "passive"))
      (node (ref "U$2") (pin "48") (pinfunction "48-PB3/I2C0SDA/T3CCP1_48") (pintype "bidirectional"))
      (node (ref "U$3") (pin "2") (pinfunction "SDA_2") (pintype "bidirectional"))
    )
    (net (code "95") (name "SERVO1") (class "Default")
      (node (ref "SERVO1") (pin "1") (pinfunction "1_1") (pintype "passive"))
      (node (ref "U$2") (pin "1") (pinfunction "1-PB6/M0PWM0/SSI2RX/T0CCP0_1") (pintype "bidirectional"))
    )
    (net (code "96") (name "SERVO2") (class "Default")
      (node (ref "SERVO2") (pin "1") (pinfunction "1_1") (pintype "passive"))
      (node (ref "U$2") (pin "4") (pinfunction "4-PB7/M0PWM1/SSI2TX/T0CCP1_4") (pintype "bidirectional"))
    )
    (net (code "97") (name "SERVO3") (class "Default")
      (node (ref "SERVO3") (pin "1") (pinfunction "1_1") (pintype "passive"))
      (node (ref "U$2") (pin "24") (pinfunction "24-PA7/I2C1SDA/M1PWM3_24") (pintype "bidirectional"))
    )
    (net (code "98") (name "SHARP1") (class "Default")
      (node (ref "U$1") (pin "11") (pinfunction "11_11") (pintype "output"))
      (node (ref "U$1") (pin "11'") (pinfunction "11'_11'") (pintype "output"))
      (node (ref "U3") (pin "3") (pinfunction "+IN_3") (pintype "input"))
    )
    (net (code "99") (name "SHARP2") (class "Default")
      (node (ref "U$1") (pin "15") (pinfunction "15_15") (pintype "output"))
      (node (ref "U$1") (pin "15'") (pinfunction "15'_15'") (pintype "output"))
      (node (ref "U3") (pin "10") (pinfunction "+IN_10") (pintype "input"))
    )
    (net (code "100") (name "SHARP3") (class "Default")
      (node (ref "U$1") (pin "41") (pinfunction "41_41") (pintype "output"))
      (node (ref "U$1") (pin "41'") (pinfunction "41'_41'") (pintype "output"))
      (node (ref "U3") (pin "5") (pinfunction "+IN_5") (pintype "input"))
    )
    (net (code "101") (name "SHARP4") (class "Default")
      (node (ref "U$1") (pin "44") (pinfunction "44_44") (pintype "output"))
      (node (ref "U$1") (pin "44'") (pinfunction "44'_44'") (pintype "output"))
      (node (ref "U3") (pin "12") (pinfunction "+IN_12") (pintype "input"))
    )
    (net (code "102") (name "SHARP5") (class "Default")
      (node (ref "U$1") (pin "45") (pinfunction "45_45") (pintype "output"))
      (node (ref "U$1") (pin "45'") (pinfunction "45'_45'") (pintype "output"))
      (node (ref "U2") (pin "3") (pinfunction "+IN_3") (pintype "input"))
    )
    (net (code "103") (name "TX") (class "Default")
      (node (ref "JP1") (pin "3") (pinfunction "3_3") (pintype "passive"))
      (node (ref "U$2") (pin "18") (pinfunction "18-PA1/CAN1TX/U0TX_18") (pintype "bidirectional"))
    )
    (net (code "104") (name "TXD") (class "Default")
      (node (ref "U$2") (pin "15") (pinfunction "15-PC5/C1+M0PWM7/PHA1/U1CTS/U1TX/U4TX/WT0CCP1_15") (pintype "bidirectional"))
      (node (ref "U1") (pin "5") (pinfunction "RXD_5") (pintype "input"))
    )
    (net (code "105") (name "USB+") (class "Default")
      (node (ref "U$1") (pin "4") (pinfunction "4_4") (pintype "output"))
      (node (ref "U$1") (pin "4'") (pinfunction "4'_4'") (pintype "output"))
      (node (ref "U1") (pin "15") (pinfunction "USBDP_15") (pintype "bidirectional"))
    )
    (net (code "106") (name "USB-") (class "Default")
      (node (ref "U$1") (pin "5") (pinfunction "5_5") (pintype "output"))
      (node (ref "U$1") (pin "5'") (pinfunction "5'_5'") (pintype "output"))
      (node (ref "U1") (pin "16") (pinfunction "USBDM_16") (pintype "bidirectional"))
    )
    (net (code "107") (name "VBATTERY") (class "Default")
      (node (ref "C18") (pin "1") (pinfunction "1_1") (pintype "passive"))
      (node (ref "C4") (pin "1") (pinfunction "1_1") (pintype "passive"))
      (node (ref "IC1") (pin "3") (pinfunction "IN_3") (pintype "input"))
      (node (ref "IC2") (pin "1") (pinfunction "VI_1") (pintype "input"))
      (node (ref "U$1") (pin "29") (pinfunction "29_29") (pintype "output"))
      (node (ref "U$1") (pin "29'") (pinfunction "29'_29'") (pintype "output"))
    )
    (net (code "108") (name "VDD") (class "Default")
      (node (ref "3.3V") (pin "1") (pinfunction "1_1") (pintype "passive"))
      (node (ref "C11") (pin "1") (pinfunction "1_1") (pintype "passive"))
      (node (ref "C12") (pin "1") (pinfunction "1_1") (pintype "passive"))
      (node (ref "C13") (pin "1") (pinfunction "1_1") (pintype "passive"))
      (node (ref "C14") (pin "1") (pinfunction "1_1") (pintype "passive"))
      (node (ref "C5") (pin "1") (pinfunction "1_1") (pintype "passive"))
      (node (ref "C7") (pin "1") (pinfunction "1_1") (pintype "passive"))
      (node (ref "C8") (pin "1") (pinfunction "1_1") (pintype "passive"))
      (node (ref "IC1") (pin "2") (pinfunction "OUT_2") (pintype "passive"))
      (node (ref "IC3") (pin "9") (pinfunction "VDD_9") (pintype "power_in"))
      (node (ref "Q1") (pin "1") (pinfunction "G_1") (pintype "passive"))
      (node (ref "Q2") (pin "1") (pinfunction "G_1") (pintype "passive"))
      (node (ref "R1") (pin "1") (pinfunction "1_1") (pintype "passive"))
      (node (ref "R2") (pin "1") (pinfunction "1_1") (pintype "passive"))
      (node (ref "R20") (pin "1") (pinfunction "1_1") (pintype "passive"))
      (node (ref "R22") (pin "1") (pinfunction "1_1") (pintype "passive"))
      (node (ref "R5") (pin "1") (pinfunction "1_1") (pintype "passive"))
      (node (ref "R8") (pin "2") (pinfunction "2_2") (pintype "passive"))
      (node (ref "R9") (pin "2") (pinfunction "2_2") (pintype "passive"))
      (node (ref "U$2") (pin "11") (pinfunction "11-VDD_11") (pintype "bidirectional"))
      (node (ref "U$2") (pin "2") (pinfunction "2-VDDA_2") (pintype "bidirectional"))
      (node (ref "U$2") (pin "26") (pinfunction "26-VDD_26") (pintype "bidirectional"))
      (node (ref "U$2") (pin "37") (pinfunction "37-VBAT_37") (pintype "bidirectional"))
      (node (ref "U$2") (pin "42") (pinfunction "42-VDD_42") (pintype "bidirectional"))
      (node (ref "U$2") (pin "54") (pinfunction "54-VDD_54") (pintype "bidirectional"))
      (node (ref "U$3") (pin "1") (pinfunction "VREF_1") (pintype "bidirectional"))
      (node (ref "U$3") (pin "5") (pinfunction "V+_5") (pintype "bidirectional"))
    )
    (net (code "109") (name "VDDC") (class "Default")
      (node (ref "C1") (pin "1") (pinfunction "1_1") (pintype "passive"))
      (node (ref "C10") (pin "1") (pinfunction "1_1") (pintype "passive"))
      (node (ref "C2") (pin "1") (pinfunction "1_1") (pintype "passive"))
      (node (ref "C3") (pin "1") (pinfunction "1_1") (pintype "passive"))
      (node (ref "U$2") (pin "25") (pinfunction "25-VDDC_25") (pintype "bidirectional"))
      (node (ref "U$2") (pin "56") (pinfunction "56-VDDC_56") (pintype "bidirectional"))
    )
    (net (code "110") (name "VSERVO") (class "Default")
      (node (ref "5V") (pin "1") (pinfunction "1_1") (pintype "passive"))
      (node (ref "C19") (pin "1") (pinfunction "1_1") (pintype "passive"))
      (node (ref "IC2") (pin "3") (pinfunction "VO_3") (pintype "passive"))
      (node (ref "R21") (pin "1") (pinfunction "1_1") (pintype "passive"))
      (node (ref "R23") (pin "1") (pinfunction "1_1") (pintype "passive"))
      (node (ref "SERVO1") (pin "2") (pinfunction "2_2") (pintype "passive"))
      (node (ref "SERVO2") (pin "2") (pinfunction "2_2") (pintype "passive"))
      (node (ref "SERVO3") (pin "2") (pinfunction "2_2") (pintype "passive"))
      (node (ref "U2") (pin "8") (pinfunction "P$V+_8") (pintype "bidirectional"))
      (node (ref "U3") (pin "4") (pinfunction "P$V+_4") (pintype "bidirectional"))
    )
    (net (code "111") (name "VUSB") (class "Default")
      (node (ref "U$1") (pin "6") (pinfunction "6_6") (pintype "output"))
      (node (ref "U1") (pin "20") (pinfunction "VCC_20") (pintype "power_in"))
    )
    (net (code "112") (name "WL1") (class "Default")
      (node (ref "U$1") (pin "30") (pinfunction "30_30") (pintype "output"))
      (node (ref "U$1") (pin "30'") (pinfunction "30'_30'") (pintype "output"))
      (node (ref "U$2") (pin "63") (pinfunction "63-PD2/AIN5/M0FAULT0/SSI1RX/SSI3RX/USB0EPEN/WT3CCP0_63") (pintype "bidirectional"))
    )
    (net (code "113") (name "WL2") (class "Default")
      (node (ref "U$1") (pin "31") (pinfunction "31_31") (pintype "output"))
      (node (ref "U$1") (pin "31'") (pinfunction "31'_31'") (pintype "output"))
      (node (ref "U$2") (pin "62") (pinfunction "62-PD1/AIN6/I2C3SDA/M0PWM7/M1PWM1/SSI1FSS/SSI3FSS/WT2CCP1_62") (pintype "bidirectional"))
    )
    (net (code "114") (name "WL3") (class "Default")
      (node (ref "U$1") (pin "32") (pinfunction "32_32") (pintype "output"))
      (node (ref "U$1") (pin "32'") (pinfunction "32'_32'") (pintype "output"))
      (node (ref "U$2") (pin "61") (pinfunction "61-PD0/AIN7/I2C3SCL/M0PWM6/M1PWM0/SSI1CLK/SSI3CLK/WT2CCP0_61") (pintype "bidirectional"))
    )
    (net (code "115") (name "WL4") (class "Default")
      (node (ref "U$1") (pin "36") (pinfunction "36_36") (pintype "output"))
      (node (ref "U$1") (pin "36'") (pinfunction "36'_36'") (pintype "output"))
      (node (ref "U$3") (pin "15") (pinfunction "IN1_15") (pintype "bidirectional"))
    )
    (net (code "116") (name "WL5") (class "Default")
      (node (ref "U$1") (pin "37") (pinfunction "37_37") (pintype "output"))
      (node (ref "U$1") (pin "37'") (pinfunction "37'_37'") (pintype "output"))
      (node (ref "U$3") (pin "14") (pinfunction "IN2_14") (pintype "bidirectional"))
    )
    (net (code "117") (name "WL6") (class "Default")
      (node (ref "U$1") (pin "38") (pinfunction "38_38") (pintype "output"))
      (node (ref "U$1") (pin "38'") (pinfunction "38'_38'") (pintype "output"))
      (node (ref "U$3") (pin "13") (pinfunction "IN3_13") (pintype "bidirectional"))
    )
    (net (code "118") (name "WL7") (class "Default")
      (node (ref "U$1") (pin "39") (pinfunction "39_39") (pintype "output"))
      (node (ref "U$1") (pin "39'") (pinfunction "39'_39'") (pintype "output"))
      (node (ref "U$3") (pin "12") (pinfunction "IN4_12") (pintype "bidirectional"))
    )
    (net (code "119") (name "ZIGBEERX") (class "Default")
      (node (ref "U$1") (pin "13") (pinfunction "13_13") (pintype "output"))
      (node (ref "U$1") (pin "13'") (pinfunction "13'_13'") (pintype "output"))
      (node (ref "U$2") (pin "13") (pinfunction "13-PC7/CO-/U3TX/USB0PFLT/WT1CCP1_13") (pintype "bidirectional"))
    )
    (net (code "120") (name "ZIGBEETX") (class "Default")
      (node (ref "U$1") (pin "14") (pinfunction "14_14") (pintype "output"))
      (node (ref "U$1") (pin "14'") (pinfunction "14'_14'") (pintype "output"))
      (node (ref "U$2") (pin "14") (pinfunction "14-PC6/C0+/PHB1/U3RX/USB0EPEN/WT1CCP0_14") (pintype "bidirectional"))
    )
    (net (code "121") (name "unconnected-(IC1-OUT1-PadTAB)") (class "Default")
      (node (ref "IC1") (pin "TAB") (pinfunction "OUT1_TAB") (pintype "passive"))
    )
    (net (code "122") (name "unconnected-(U$1-Pad6')") (class "Default")
      (node (ref "U$1") (pin "6'") (pinfunction "6'_6'") (pintype "output"))
    )
    (net (code "123") (name "unconnected-(U$1-Pad7)") (class "Default")
      (node (ref "U$1") (pin "7") (pinfunction "7_7") (pintype "output"))
    )
    (net (code "124") (name "unconnected-(U$1-Pad7A)") (class "Default")
      (node (ref "U$1") (pin "7A") (pinfunction "7A_7A") (pintype "output"))
    )
    (net (code "125") (name "unconnected-(U$1-Pad8)") (class "Default")
      (node (ref "U$1") (pin "8") (pinfunction "8_8") (pintype "output"))
    )
    (net (code "126") (name "unconnected-(U$1-Pad8A)") (class "Default")
      (node (ref "U$1") (pin "8A") (pinfunction "8A_8A") (pintype "output"))
    )
    (net (code "127") (name "unconnected-(U$1-Pad9)") (class "Default")
      (node (ref "U$1") (pin "9") (pinfunction "9_9") (pintype "output"))
    )
    (net (code "128") (name "unconnected-(U$1-Pad9A)") (class "Default")
      (node (ref "U$1") (pin "9A") (pinfunction "9A_9A") (pintype "output"))
    )
    (net (code "129") (name "unconnected-(U$1-Pad10)") (class "Default")
      (node (ref "U$1") (pin "10") (pinfunction "10_10") (pintype "output"))
    )
    (net (code "130") (name "unconnected-(U$1-Pad10A)") (class "Default")
      (node (ref "U$1") (pin "10A") (pinfunction "10A_10A") (pintype "output"))
    )
    (net (code "131") (name "unconnected-(U$1-Pad17A)") (class "Default")
      (node (ref "U$1") (pin "17A") (pinfunction "17A_17A") (pintype "output"))
    )
    (net (code "132") (name "unconnected-(U$1-Pad17B)") (class "Default")
      (node (ref "U$1") (pin "17B") (pinfunction "17B_17B") (pintype "output"))
    )
    (net (code "133") (name "unconnected-(U$1-Pad20)") (class "Default")
      (node (ref "U$1") (pin "20") (pinfunction "20_20") (pintype "output"))
    )
    (net (code "134") (name "unconnected-(U$1-Pad20A)") (class "Default")
      (node (ref "U$1") (pin "20A") (pinfunction "20A_20A") (pintype "output"))
    )
    (net (code "135") (name "unconnected-(U$1-Pad21)") (class "Default")
      (node (ref "U$1") (pin "21") (pinfunction "21_21") (pintype "output"))
    )
    (net (code "136") (name "unconnected-(U$1-Pad21A)") (class "Default")
      (node (ref "U$1") (pin "21A") (pinfunction "21A_21A") (pintype "output"))
    )
    (net (code "137") (name "unconnected-(U$1-Pad35)") (class "Default")
      (node (ref "U$1") (pin "35") (pinfunction "35_35") (pintype "output"))
    )
    (net (code "138") (name "unconnected-(U$1-Pad35A)") (class "Default")
      (node (ref "U$1") (pin "35A") (pinfunction "35A_35A") (pintype "output"))
    )
    (net (code "139") (name "unconnected-(U$1-Pad57)") (class "Default")
      (node (ref "U$1") (pin "57") (pinfunction "57_57") (pintype "output"))
    )
    (net (code "140") (name "unconnected-(U$1-Pad57A)") (class "Default")
      (node (ref "U$1") (pin "57A") (pinfunction "57A_57A") (pintype "output"))
    )
    (net (code "141") (name "unconnected-(U$1-Pad58)") (class "Default")
      (node (ref "U$1") (pin "58") (pinfunction "58_58") (pintype "output"))
    )
    (net (code "142") (name "unconnected-(U$1-Pad58A)") (class "Default")
      (node (ref "U$1") (pin "58A") (pinfunction "58A_58A") (pintype "output"))
    )
    (net (code "143") (name "unconnected-(U$1-Pad59)") (class "Default")
      (node (ref "U$1") (pin "59") (pinfunction "59_59") (pintype "output"))
    )
    (net (code "144") (name "unconnected-(U$1-Pad59A)") (class "Default")
      (node (ref "U$1") (pin "59A") (pinfunction "59A_59A") (pintype "output"))
    )
    (net (code "145") (name "unconnected-(U$1-Pad60)") (class "Default")
      (node (ref "U$1") (pin "60") (pinfunction "60_60") (pintype "output"))
    )
    (net (code "146") (name "unconnected-(U$1-Pad60A)") (class "Default")
      (node (ref "U$1") (pin "60A") (pinfunction "60A_60A") (pintype "output"))
    )
    (net (code "147") (name "unconnected-(U$1-Pad72')") (class "Default")
      (node (ref "U$1") (pin "72'") (pinfunction "72'_72'") (pintype "output"))
    )
    (net (code "148") (name "unconnected-(U$1-Pad72)") (class "Default")
      (node (ref "U$1") (pin "72") (pinfunction "72_72") (pintype "output"))
    )
    (net (code "149") (name "unconnected-(U$2-32-WAKE-Pad32)") (class "Default")
      (node (ref "U$2") (pin "32") (pinfunction "32-WAKE_32") (pintype "bidirectional"))
    )
    (net (code "150") (name "unconnected-(U$2-33-HIB-Pad33)") (class "Default")
      (node (ref "U$2") (pin "33") (pinfunction "33-HIB_33") (pintype "bidirectional"))
    )
    (net (code "151") (name "unconnected-(U1-CTS-Pad11)") (class "Default")
      (node (ref "U1") (pin "11") (pinfunction "CTS_11") (pintype "bidirectional"))
    )
    (net (code "152") (name "unconnected-(U1-DTR-Pad2)") (class "Default")
      (node (ref "U1") (pin "2") (pinfunction "DTR_2") (pintype "bidirectional"))
    )
    (net (code "153") (name "unconnected-(U1-RTS-Pad3)") (class "Default")
      (node (ref "U1") (pin "3") (pinfunction "RTS_3") (pintype "bidirectional"))
    )
    (net (code "154") (name "unconnected-(U2B-+IN-Pad5)") (class "Default")
      (node (ref "U2") (pin "5") (pinfunction "+IN_5") (pintype "input"))
    )
  )
)
